# zhuanjieban.net
KiCad netlist of a schematic drawn in Altium Designer
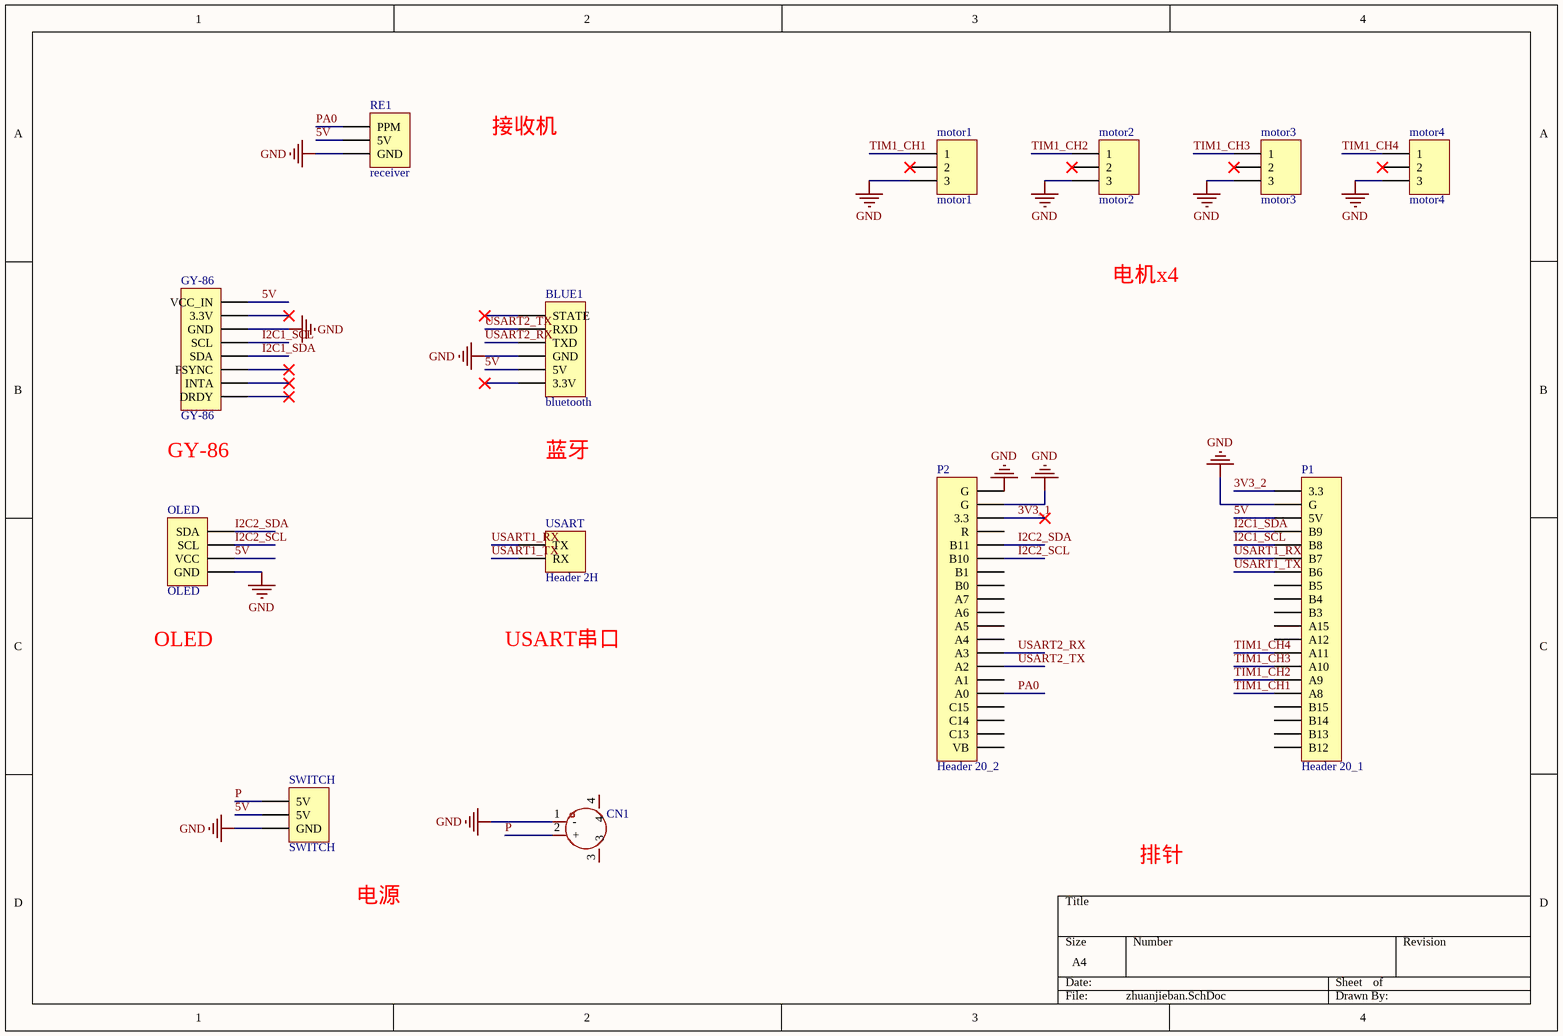
[diagram p0: zhuanjieban.SchDoc]

(export (version "E")
  (design (tool "Eeschema 10.0.6"))
  (components
    (comp (ref "BLUE1")
      (value "bluetooth")
      (footprint "HDR1X6")
      (description "Header, 6-Pin")
      (fields (field (name "PUBLISHER") "Altium Limited"))
      (libsource (lib "Miscellaneous Connectors") (part "Header 6"))
    )
    (comp (ref "CN1")
      (value "~")
      (footprint "PCBComponent_1")
      (libsource (lib "Schlib2") (part "Component_1"))
    )
    (comp (ref "GY-86")
      (value "GY-86")
      (footprint "HDR1X8")
      (description "Header, 8-Pin")
      (fields (field (name "PUBLISHER") "Altium Limited"))
      (libsource (lib "Miscellaneous Connectors") (part "Header 8"))
    )
    (comp (ref "motor1")
      (value "motor1")
      (footprint "HDR1X3")
      (description "Header, 3-Pin")
      (fields (field (name "PUBLISHER") "Altium Limited"))
      (libsource (lib "Miscellaneous Connectors") (part "Header 3"))
    )
    (comp (ref "motor2")
      (value "motor2")
      (footprint "HDR1X3")
      (description "Header, 3-Pin")
      (fields (field (name "PUBLISHER") "Altium Limited"))
      (libsource (lib "Miscellaneous Connectors") (part "Header 3"))
    )
    (comp (ref "motor3")
      (value "motor3")
      (footprint "HDR1X3")
      (description "Header, 3-Pin")
      (fields (field (name "PUBLISHER") "Altium Limited"))
      (libsource (lib "Miscellaneous Connectors") (part "Header 3"))
    )
    (comp (ref "motor4")
      (value "motor4")
      (footprint "HDR1X3")
      (description "Header, 3-Pin")
      (fields (field (name "PUBLISHER") "Altium Limited"))
      (libsource (lib "Miscellaneous Connectors") (part "Header 3"))
    )
    (comp (ref "OLED")
      (value "OLED")
      (footprint "HDR1X4")
      (description "Header, 4-Pin")
      (fields (field (name "PUBLISHER") "Altium Limited"))
      (libsource (lib "Miscellaneous Connectors") (part "Header 4"))
    )
    (comp (ref "P1")
      (value "Header 20_1")
      (footprint "HDR1X20")
      (fields (field (name "PUBLISHER") "Altium Limited"))
      (libsource (lib "") (part "Header1* 20_1"))
    )
    (comp (ref "P2")
      (value "Header 20_2")
      (footprint "HDR1X20")
      (fields (field (name "PUBLISHER") "Altium Limited"))
      (libsource (lib "stm32原理图库") (part "Header1* 20"))
    )
    (comp (ref "RE1")
      (value "receiver")
      (footprint "HDR1X3")
      (description "Header, 3-Pin")
      (fields (field (name "PUBLISHER") "Altium Limited"))
      (libsource (lib "Miscellaneous Connectors") (part "Header 3"))
    )
    (comp (ref "SWITCH")
      (value "SWITCH")
      (footprint "HDR1X3")
      (description "Header, 3-Pin")
      (fields (field (name "PUBLISHER") "Altium Limited"))
      (libsource (lib "Miscellaneous Connectors") (part "Header 3"))
    )
    (comp (ref "USART")
      (value "Header 2H")
      (footprint "HDR1X2H")
      (description "Header, 2-Pin, Right Angle")
      (fields (field (name "PUBLISHER") "Altium Limited"))
      (libsource (lib "Miscellaneous Connectors") (part "Header 2H"))
    )
  )
  (nets
    (net (code "1") (name "/3V3_1") (class "Default")
      (node (ref "P2") (pin "18") (pinfunction "3.3_18") (pintype "passive+no_connect"))
    )
    (net (code "2") (name "/3V3_2") (class "Default")
      (node (ref "P1") (pin "1") (pinfunction "3.3_1") (pintype "passive"))
    )
    (net (code "3") (name "/5V") (class "Default")
      (node (ref "BLUE1") (pin "5") (pinfunction "5V_5") (pintype "passive"))
      (node (ref "GY-86") (pin "8") (pinfunction "VCC_IN_8") (pintype "passive"))
      (node (ref "OLED") (pin "2") (pinfunction "VCC_2") (pintype "passive"))
      (node (ref "P1") (pin "3") (pinfunction "5V_3") (pintype "passive"))
      (node (ref "RE1") (pin "2") (pinfunction "5V_2") (pintype "passive"))
      (node (ref "SWITCH") (pin "2") (pinfunction "5V_2") (pintype "passive"))
    )
    (net (code "4") (name "/I2C1_SCL") (class "Default")
      (node (ref "GY-86") (pin "5") (pinfunction "SCL_5") (pintype "passive"))
      (node (ref "P1") (pin "5") (pinfunction "B8_5") (pintype "passive"))
    )
    (net (code "5") (name "/I2C1_SDA") (class "Default")
      (node (ref "GY-86") (pin "4") (pinfunction "SDA_4") (pintype "passive"))
      (node (ref "P1") (pin "4") (pinfunction "B9_4") (pintype "passive"))
    )
    (net (code "6") (name "/I2C2_SCL") (class "Default")
      (node (ref "OLED") (pin "3") (pinfunction "SCL_3") (pintype "passive"))
      (node (ref "P2") (pin "15") (pinfunction "B10_15") (pintype "passive"))
    )
    (net (code "7") (name "/I2C2_SDA") (class "Default")
      (node (ref "OLED") (pin "4") (pinfunction "SDA_4") (pintype "passive"))
      (node (ref "P2") (pin "16") (pinfunction "B11_16") (pintype "passive"))
    )
    (net (code "8") (name "/P") (class "Default")
      (node (ref "CN1") (pin "2") (pinfunction "+_2") (pintype "passive"))
      (node (ref "SWITCH") (pin "1") (pinfunction "PPM_1") (pintype "passive"))
    )
    (net (code "9") (name "/PA0") (class "Default")
      (node (ref "P2") (pin "5") (pinfunction "A0_5") (pintype "passive"))
      (node (ref "RE1") (pin "1") (pinfunction "PPM_1") (pintype "passive"))
    )
    (net (code "10") (name "/TIM1_CH1") (class "Default")
      (node (ref "P1") (pin "16") (pinfunction "A8_16") (pintype "passive"))
      (node (ref "motor1") (pin "1") (pinfunction "PPM_1") (pintype "passive"))
    )
    (net (code "11") (name "/TIM1_CH2") (class "Default")
      (node (ref "P1") (pin "15") (pinfunction "A9_15") (pintype "passive"))
      (node (ref "motor2") (pin "1") (pinfunction "PPM_1") (pintype "passive"))
    )
    (net (code "12") (name "/TIM1_CH3") (class "Default")
      (node (ref "P1") (pin "14") (pinfunction "A10_14") (pintype "passive"))
      (node (ref "motor3") (pin "1") (pinfunction "PPM_1") (pintype "passive"))
    )
    (net (code "13") (name "/TIM1_CH4") (class "Default")
      (node (ref "P1") (pin "13") (pinfunction "A11_13") (pintype "passive"))
      (node (ref "motor4") (pin "1") (pinfunction "PPM_1") (pintype "passive"))
    )
    (net (code "14") (name "/USART1_RX") (class "Default")
      (node (ref "P1") (pin "6") (pinfunction "B7_6") (pintype "passive"))
      (node (ref "USART") (pin "1") (pinfunction "TX_1") (pintype "passive"))
    )
    (net (code "15") (name "/USART1_TX") (class "Default")
      (node (ref "P1") (pin "7") (pinfunction "B6_7") (pintype "passive"))
      (node (ref "USART") (pin "2") (pinfunction "RX_2") (pintype "passive"))
    )
    (net (code "16") (name "/USART2_RX") (class "Default")
      (node (ref "BLUE1") (pin "3") (pinfunction "TXD_3") (pintype "passive"))
      (node (ref "P2") (pin "8") (pinfunction "A3_8") (pintype "passive"))
    )
    (net (code "17") (name "/USART2_TX") (class "Default")
      (node (ref "BLUE1") (pin "2") (pinfunction "RXD_2") (pintype "passive"))
      (node (ref "P2") (pin "7") (pinfunction "A2_7") (pintype "passive"))
    )
    (net (code "18") (name "GND") (class "Default")
      (node (ref "BLUE1") (pin "4") (pinfunction "GND_4") (pintype "passive"))
      (node (ref "CN1") (pin "1") (pinfunction "-_1") (pintype "passive"))
      (node (ref "GY-86") (pin "6") (pinfunction "GND_6") (pintype "passive"))
      (node (ref "OLED") (pin "1") (pinfunction "GND_1") (pintype "passive"))
      (node (ref "P1") (pin "2") (pinfunction "G_2") (pintype "passive"))
      (node (ref "P2") (pin "19") (pinfunction "G_19") (pintype "passive"))
      (node (ref "P2") (pin "20") (pinfunction "G_20") (pintype "passive"))
      (node (ref "RE1") (pin "3") (pinfunction "GND_3") (pintype "passive"))
      (node (ref "SWITCH") (pin "3") (pinfunction "GND_3") (pintype "passive"))
      (node (ref "motor1") (pin "3") (pinfunction "GND_3") (pintype "passive"))
      (node (ref "motor2") (pin "3") (pinfunction "GND_3") (pintype "passive"))
      (node (ref "motor3") (pin "3") (pinfunction "GND_3") (pintype "passive"))
      (node (ref "motor4") (pin "3") (pinfunction "GND_3") (pintype "passive"))
    )
    (net (code "19") (name "unconnected-(BLUE1-3.3V-Pad6)") (class "Default")
      (node (ref "BLUE1") (pin "6") (pinfunction "3.3V_6") (pintype "passive+no_connect"))
    )
    (net (code "20") (name "unconnected-(BLUE1-STATE-Pad1)") (class "Default")
      (node (ref "BLUE1") (pin "1") (pinfunction "STATE_1") (pintype "passive+no_connect"))
    )
    (net (code "21") (name "unconnected-(CN1-Pad3)") (class "Default")
      (node (ref "CN1") (pin "3") (pinfunction "3_3") (pintype "passive"))
    )
    (net (code "22") (name "unconnected-(CN1-Pad4)") (class "Default")
      (node (ref "CN1") (pin "4") (pinfunction "4_4") (pintype "passive"))
    )
    (net (code "23") (name "unconnected-(GY-86-3.3V-Pad7)") (class "Default")
      (node (ref "GY-86") (pin "7") (pinfunction "3.3V_7") (pintype "passive+no_connect"))
    )
    (net (code "24") (name "unconnected-(GY-86-DRDY-Pad1)") (class "Default")
      (node (ref "GY-86") (pin "1") (pinfunction "DRDY_1") (pintype "passive+no_connect"))
    )
    (net (code "25") (name "unconnected-(GY-86-FSYNC-Pad3)") (class "Default")
      (node (ref "GY-86") (pin "3") (pinfunction "FSYNC_3") (pintype "passive+no_connect"))
    )
    (net (code "26") (name "unconnected-(GY-86-INTA-Pad2)") (class "Default")
      (node (ref "GY-86") (pin "2") (pinfunction "INTA_2") (pintype "passive+no_connect"))
    )
    (net (code "27") (name "unconnected-(P1-A12-Pad12)") (class "Default")
      (node (ref "P1") (pin "12") (pinfunction "A12_12") (pintype "passive"))
    )
    (net (code "28") (name "unconnected-(P1-A15-Pad11)") (class "Default")
      (node (ref "P1") (pin "11") (pinfunction "A15_11") (pintype "passive"))
    )
    (net (code "29") (name "unconnected-(P1-B3-Pad10)") (class "Default")
      (node (ref "P1") (pin "10") (pinfunction "B3_10") (pintype "passive"))
    )
    (net (code "30") (name "unconnected-(P1-B4-Pad9)") (class "Default")
      (node (ref "P1") (pin "9") (pinfunction "B4_9") (pintype "passive"))
    )
    (net (code "31") (name "unconnected-(P1-B5-Pad8)") (class "Default")
      (node (ref "P1") (pin "8") (pinfunction "B5_8") (pintype "passive"))
    )
    (net (code "32") (name "unconnected-(P1-B12-Pad20)") (class "Default")
      (node (ref "P1") (pin "20") (pinfunction "B12_20") (pintype "passive"))
    )
    (net (code "33") (name "unconnected-(P1-B13-Pad19)") (class "Default")
      (node (ref "P1") (pin "19") (pinfunction "B13_19") (pintype "passive"))
    )
    (net (code "34") (name "unconnected-(P1-B14-Pad18)") (class "Default")
      (node (ref "P1") (pin "18") (pinfunction "B14_18") (pintype "passive"))
    )
    (net (code "35") (name "unconnected-(P1-B15-Pad17)") (class "Default")
      (node (ref "P1") (pin "17") (pinfunction "B15_17") (pintype "passive"))
    )
    (net (code "36") (name "unconnected-(P2-A1-Pad6)") (class "Default")
      (node (ref "P2") (pin "6") (pinfunction "A1_6") (pintype "passive"))
    )
    (net (code "37") (name "unconnected-(P2-A4-Pad9)") (class "Default")
      (node (ref "P2") (pin "9") (pinfunction "A4_9") (pintype "passive"))
    )
    (net (code "38") (name "unconnected-(P2-A5-Pad10)") (class "Default")
      (node (ref "P2") (pin "10") (pinfunction "A5_10") (pintype "passive"))
    )
    (net (code "39") (name "unconnected-(P2-A6-Pad11)") (class "Default")
      (node (ref "P2") (pin "11") (pinfunction "A6_11") (pintype "passive"))
    )
    (net (code "40") (name "unconnected-(P2-A7-Pad12)") (class "Default")
      (node (ref "P2") (pin "12") (pinfunction "A7_12") (pintype "passive"))
    )
    (net (code "41") (name "unconnected-(P2-B0-Pad13)") (class "Default")
      (node (ref "P2") (pin "13") (pinfunction "B0_13") (pintype "passive"))
    )
    (net (code "42") (name "unconnected-(P2-B1-Pad14)") (class "Default")
      (node (ref "P2") (pin "14") (pinfunction "B1_14") (pintype "passive"))
    )
    (net (code "43") (name "unconnected-(P2-C13-Pad2)") (class "Default")
      (node (ref "P2") (pin "2") (pinfunction "C13_2") (pintype "passive"))
    )
    (net (code "44") (name "unconnected-(P2-C14-Pad3)") (class "Default")
      (node (ref "P2") (pin "3") (pinfunction "C14_3") (pintype "passive"))
    )
    (net (code "45") (name "unconnected-(P2-C15-Pad4)") (class "Default")
      (node (ref "P2") (pin "4") (pinfunction "C15_4") (pintype "passive"))
    )
    (net (code "46") (name "unconnected-(P2-R-Pad17)") (class "Default")
      (node (ref "P2") (pin "17") (pinfunction "R_17") (pintype "passive"))
    )
    (net (code "47") (name "unconnected-(P2-VB-Pad1)") (class "Default")
      (node (ref "P2") (pin "1") (pinfunction "VB_1") (pintype "passive"))
    )
    (net (code "48") (name "unconnected-(motor1-5V-Pad2)") (class "Default")
      (node (ref "motor1") (pin "2") (pinfunction "5V_2") (pintype "passive+no_connect"))
    )
    (net (code "49") (name "unconnected-(motor2-5V-Pad2)") (class "Default")
      (node (ref "motor2") (pin "2") (pinfunction "5V_2") (pintype "passive+no_connect"))
    )
    (net (code "50") (name "unconnected-(motor3-5V-Pad2)") (class "Default")
      (node (ref "motor3") (pin "2") (pinfunction "5V_2") (pintype "passive+no_connect"))
    )
    (net (code "51") (name "unconnected-(motor4-5V-Pad2)") (class "Default")
      (node (ref "motor4") (pin "2") (pinfunction "5V_2") (pintype "passive+no_connect"))
    )
  )
)
